# TGA3042.net
KiCad netlist of a schematic drawn in Altium Designer
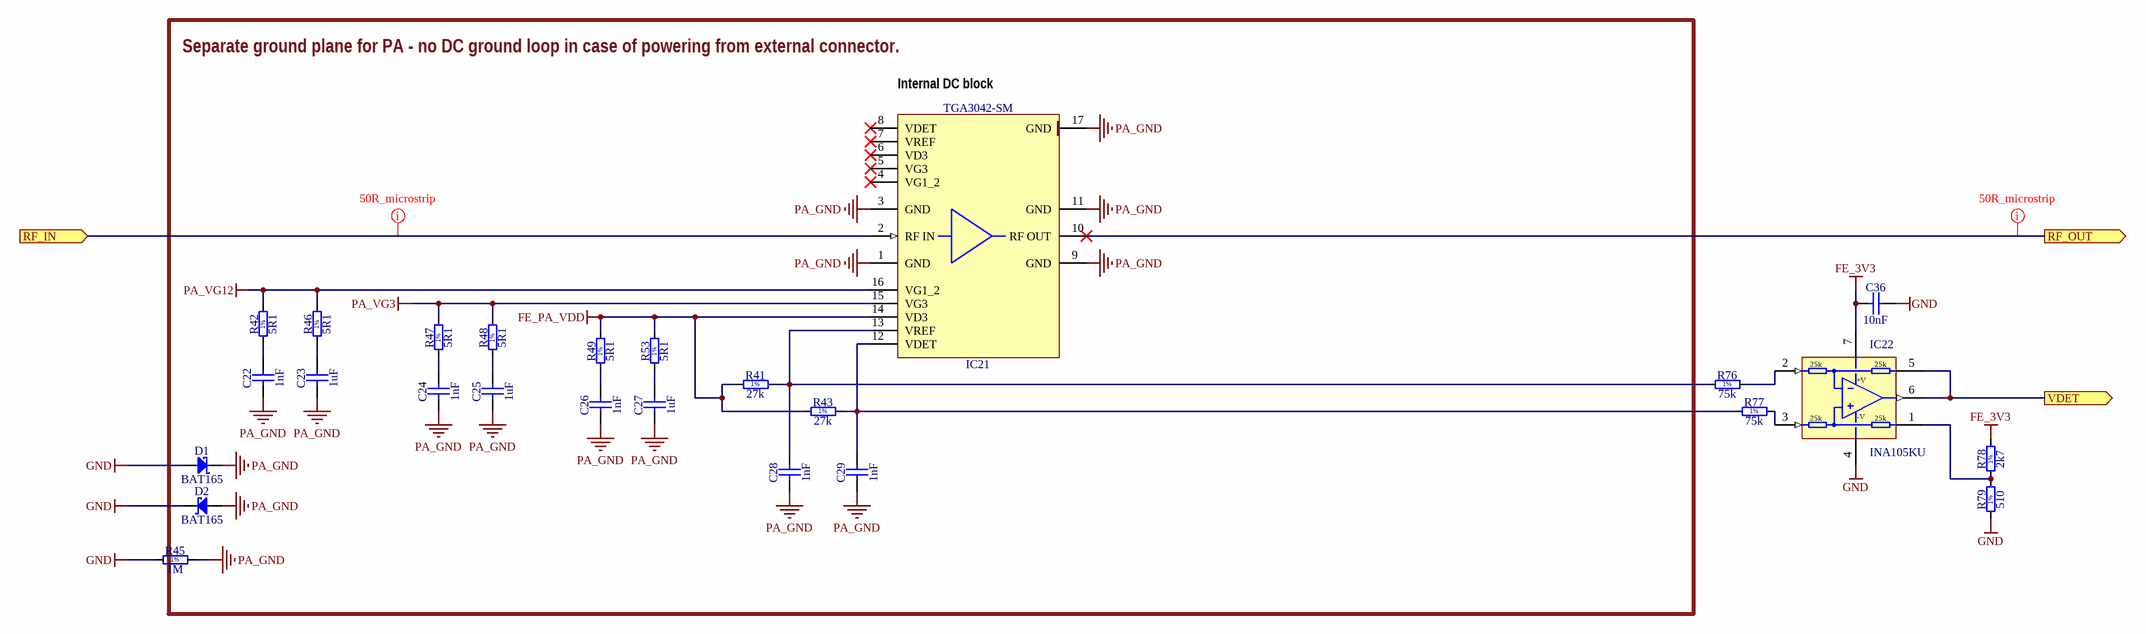
[diagram p0: TGA3042.SchDoc]

(export (version "E")
  (design (tool "Eeschema 10.0.6"))
  (components
    (comp (ref "C22")
      (value "1nF")
      (footprint "CAPC1005X55N")
      (description "Non-polarised capacitor")
      (fields
        (field (name "PART NUMBER") "CC0402_1NF_50V_10%_X7R")
        (field (name "VOLTAGE") "50V")
        (field (name "AUTHOR") "CERN DEM JLC")
      )
      (libsource (lib "Capacitors") (part "Capacitor - non polarized"))
    )
    (comp (ref "C23")
      (value "1uF")
      (footprint "CAPC3216X140N")
      (description "Non-polarised capacitor")
      (fields
        (field (name "PART NUMBER") "CC1206_1UF_50V_10%_X7R")
        (field (name "VOLTAGE") "50V")
        (field (name "AUTHOR") "CERN DEM JLC")
      )
      (libsource (lib "Capacitors") (part "Capacitor - non polarized"))
    )
    (comp (ref "C24")
      (value "1nF")
      (footprint "CAPC1005X55N")
      (description "Non-polarised capacitor")
      (fields
        (field (name "PART NUMBER") "CC0402_1NF_50V_10%_X7R")
        (field (name "VOLTAGE") "50V")
        (field (name "AUTHOR") "CERN DEM JLC")
      )
      (libsource (lib "Capacitors") (part "Capacitor - non polarized"))
    )
    (comp (ref "C25")
      (value "1uF")
      (footprint "CAPC3216X140N")
      (description "Non-polarised capacitor")
      (fields
        (field (name "PART NUMBER") "CC1206_1UF_50V_10%_X7R")
        (field (name "VOLTAGE") "50V")
        (field (name "AUTHOR") "CERN DEM JLC")
      )
      (libsource (lib "Capacitors") (part "Capacitor - non polarized"))
    )
    (comp (ref "C26")
      (value "1nF")
      (footprint "CAPC1005X55N")
      (description "Non-polarised capacitor")
      (fields
        (field (name "PART NUMBER") "CC0402_1NF_50V_10%_X7R")
        (field (name "VOLTAGE") "50V")
        (field (name "AUTHOR") "CERN DEM JLC")
      )
      (libsource (lib "Capacitors") (part "Capacitor - non polarized"))
    )
    (comp (ref "C27")
      (value "1uF")
      (footprint "CAPC3216X140N")
      (description "Non-polarised capacitor")
      (fields
        (field (name "PART NUMBER") "CC1206_1UF_50V_10%_X7R")
        (field (name "VOLTAGE") "50V")
        (field (name "AUTHOR") "CERN DEM JLC")
      )
      (libsource (lib "Capacitors") (part "Capacitor - non polarized"))
    )
    (comp (ref "C28")
      (value "1nF")
      (footprint "CAPC1005X55N")
      (description "Non-polarised capacitor")
      (fields
        (field (name "PART NUMBER") "CC0402_1NF_50V_10%_X7R")
        (field (name "VOLTAGE") "50V")
        (field (name "AUTHOR") "CERN DEM JLC")
      )
      (libsource (lib "Capacitors") (part "Capacitor - non polarized"))
    )
    (comp (ref "C29")
      (value "1nF")
      (footprint "CAPC1005X55N")
      (description "Non-polarised capacitor")
      (fields
        (field (name "PART NUMBER") "CC0402_1NF_50V_10%_X7R")
        (field (name "VOLTAGE") "50V")
        (field (name "AUTHOR") "CERN DEM JLC")
      )
      (libsource (lib "Capacitors") (part "Capacitor - non polarized"))
    )
    (comp (ref "C36")
      (value "10nF")
      (footprint "CAPC1005X55N")
      (description "Non-polarised capacitor")
      (fields
        (field (name "PART NUMBER") "CC0402_10NF_50V_10%_X7R")
        (field (name "VOLTAGE") "50V")
        (field (name "AUTHOR") "CERN DEM MR")
      )
      (libsource (lib "Capacitors") (part "Capacitor - non polarized"))
    )
    (comp (ref "D1")
      (value "BAT165")
      (footprint "SOD2512X110N")
      (description "Schottky Diode")
      (fields
        (field (name "VOLTAGE") "40V")
        (field (name "POWER") "750mA")
        (field (name "AUTHOR") "CERN DEM JLC")
      )
      (libsource (lib "ICs And Semiconductors") (part "Diode Schottky"))
    )
    (comp (ref "D2")
      (value "BAT165")
      (footprint "SOD2512X110N")
      (description "Schottky Diode")
      (fields
        (field (name "VOLTAGE") "40V")
        (field (name "POWER") "750mA")
        (field (name "AUTHOR") "CERN DEM JLC")
      )
      (libsource (lib "ICs And Semiconductors") (part "Diode Schottky"))
    )
    (comp (ref "IC21")
      (value "TGA3042-SM")
      (footprint "QORVO_TGA3042-SM")
      (description "7-10.5GHz 4.5W GaN Power Amplifier")
      (fields (field (name "MANUFACTURER") "QORVO") (field (name "AUTHOR") "CERN DEM JLC"))
      (libsource (lib "FMC_SDR") (part "TGA3042-SM"))
    )
    (comp (ref "IC22")
      (value "INA105KU")
      (footprint "SOIC127P600X175-8N")
      (description "Precision, Unity-Gain Differential Amplifier")
      (fields (field (name "MANUFACTURER") "TEXAS INSTRUMENTS") (field (name "AUTHOR") "CERN DEM JLC"))
      (libsource (lib "ICs And Semiconductors") (part "INA105K"))
    )
    (comp (ref "R41")
      (value "27k")
      (footprint "RESC1005X40N")
      (description "Resistor - 1%")
      (fields
        (field (name "PART NUMBER") "R0402_27K_1%_0.0625W_100PPM")
        (field (name "POWER") "0.0625W")
        (field (name "AUTHOR") "CERN DEM JLC")
      )
      (libsource (lib "Resistors") (part "Resistor - 1%"))
    )
    (comp (ref "R42")
      (value "5R1")
      (footprint "RESC1005X40N")
      (description "Resistor - 1%")
      (fields
        (field (name "PART NUMBER") "R0402_5R1_1%_0.0625W_100PPM")
        (field (name "POWER") "0.0625W")
        (field (name "AUTHOR") "CERN DEM MR")
      )
      (libsource (lib "Resistors") (part "Resistor - 1%"))
    )
    (comp (ref "R43")
      (value "27k")
      (footprint "RESC1005X40N")
      (description "Resistor - 1%")
      (fields
        (field (name "PART NUMBER") "R0402_27K_1%_0.0625W_100PPM")
        (field (name "POWER") "0.0625W")
        (field (name "AUTHOR") "CERN DEM JLC")
      )
      (libsource (lib "Resistors") (part "Resistor - 1%"))
    )
    (comp (ref "R45")
      (value "1M")
      (footprint "RESC1005X40N")
      (description "Resistor - 1%")
      (fields
        (field (name "PART NUMBER") "R0402_1M_1%_0.0625W_100PPM")
        (field (name "POWER") "0.0625W")
        (field (name "AUTHOR") "CERN DEM JLC")
      )
      (libsource (lib "Resistors") (part "Resistor - 1%"))
    )
    (comp (ref "R46")
      (value "5R1")
      (footprint "RESC1005X40N")
      (description "Resistor - 1%")
      (fields
        (field (name "PART NUMBER") "R0402_5R1_1%_0.0625W_100PPM")
        (field (name "POWER") "0.0625W")
        (field (name "AUTHOR") "CERN DEM MR")
      )
      (libsource (lib "Resistors") (part "Resistor - 1%"))
    )
    (comp (ref "R47")
      (value "5R1")
      (footprint "RESC1005X40N")
      (description "Resistor - 1%")
      (fields
        (field (name "PART NUMBER") "R0402_5R1_1%_0.0625W_100PPM")
        (field (name "POWER") "0.0625W")
        (field (name "AUTHOR") "CERN DEM MR")
      )
      (libsource (lib "Resistors") (part "Resistor - 1%"))
    )
    (comp (ref "R48")
      (value "5R1")
      (footprint "RESC1005X40N")
      (description "Resistor - 1%")
      (fields
        (field (name "PART NUMBER") "R0402_5R1_1%_0.0625W_100PPM")
        (field (name "POWER") "0.0625W")
        (field (name "AUTHOR") "CERN DEM MR")
      )
      (libsource (lib "Resistors") (part "Resistor - 1%"))
    )
    (comp (ref "R49")
      (value "5R1")
      (footprint "RESC1005X40N")
      (description "Resistor - 1%")
      (fields
        (field (name "PART NUMBER") "R0402_5R1_1%_0.0625W_100PPM")
        (field (name "POWER") "0.0625W")
        (field (name "AUTHOR") "CERN DEM MR")
      )
      (libsource (lib "Resistors") (part "Resistor - 1%"))
    )
    (comp (ref "R53")
      (value "5R1")
      (footprint "RESC1005X40N")
      (description "Resistor - 1%")
      (fields
        (field (name "PART NUMBER") "R0402_5R1_1%_0.0625W_100PPM")
        (field (name "POWER") "0.0625W")
        (field (name "AUTHOR") "CERN DEM MR")
      )
      (libsource (lib "Resistors") (part "Resistor - 1%"))
    )
    (comp (ref "R76")
      (value "75k")
      (footprint "RESC1608X55N")
      (description "Resistor - 1%")
      (fields
        (field (name "PART NUMBER") "R0603_75K_1%_0.1W_100PPM")
        (field (name "POWER") "0.1W")
        (field (name "AUTHOR") "CERN DEM JLC")
      )
      (libsource (lib "Resistors") (part "Resistor - 1%"))
    )
    (comp (ref "R77")
      (value "75k")
      (footprint "RESC1608X55N")
      (description "Resistor - 1%")
      (fields
        (field (name "PART NUMBER") "R0603_75K_1%_0.1W_100PPM")
        (field (name "POWER") "0.1W")
        (field (name "AUTHOR") "CERN DEM JLC")
      )
      (libsource (lib "Resistors") (part "Resistor - 1%"))
    )
    (comp (ref "R78")
      (value "2k7")
      (footprint "RESC1608X55N")
      (description "Resistor - 1%")
      (fields
        (field (name "PART NUMBER") "R0603_2K7_1%_0.1W_100PPM")
        (field (name "POWER") "0.1W")
        (field (name "AUTHOR") "CERN DEM JLC")
      )
      (libsource (lib "Resistors") (part "Resistor - 1%"))
    )
    (comp (ref "R79")
      (value "510")
      (footprint "RESC1608X55N")
      (description "Resistor - 1%")
      (fields
        (field (name "PART NUMBER") "R0603_510R_1%_0.1W_100PPM")
        (field (name "POWER") "0.1W")
        (field (name "AUTHOR") "CERN DEM JLC")
      )
      (libsource (lib "Resistors") (part "Resistor - 1%"))
    )
  )
  (nets
    (net (code "1") (name "/RF_IN") (class "Default")
      (node (ref "IC21") (pin "2") (pinfunction "RF_IN_2") (pintype "input"))
    )
    (net (code "2") (name "/RF_OUT") (class "Default")
      (node (ref "IC21") (pin "10") (pinfunction "RF_OUT_10") (pintype "power_in+no_connect"))
    )
    (net (code "3") (name "/VDET") (class "Default")
      (node (ref "IC22") (pin "5") (pinfunction "SENS_5") (pintype "passive"))
      (node (ref "IC22") (pin "6") (pinfunction "OUT_6") (pintype "output"))
    )
    (net (code "4") (name "FE_3V3") (class "Default")
      (node (ref "C36") (pin "1") (pinfunction "1_1") (pintype "passive"))
      (node (ref "IC22") (pin "7") (pinfunction "+VCC_7") (pintype "power_in"))
      (node (ref "R78") (pin "2") (pinfunction "2_2") (pintype "passive"))
    )
    (net (code "5") (name "FE_PA_VDD") (class "Default")
      (node (ref "IC21") (pin "14") (pinfunction "VD3_14") (pintype "power_in"))
      (node (ref "R41") (pin "1") (pinfunction "1_1") (pintype "passive"))
      (node (ref "R43") (pin "1") (pinfunction "1_1") (pintype "passive"))
      (node (ref "R49") (pin "2") (pinfunction "2_2") (pintype "passive"))
      (node (ref "R53") (pin "2") (pinfunction "2_2") (pintype "passive"))
    )
    (net (code "6") (name "GND") (class "Default")
      (node (ref "C36") (pin "2") (pinfunction "2_2") (pintype "passive"))
      (node (ref "D1") (pin "2") (pinfunction "A_2") (pintype "passive"))
      (node (ref "D2") (pin "1") (pinfunction "C_1") (pintype "passive"))
      (node (ref "IC22") (pin "4") (pinfunction "-VEE_4") (pintype "power_in"))
      (node (ref "R45") (pin "1") (pinfunction "1_1") (pintype "passive"))
      (node (ref "R79") (pin "1") (pinfunction "1_1") (pintype "passive"))
    )
    (net (code "7") (name "Net-(C22-Pad2)") (class "Default")
      (node (ref "C22") (pin "2") (pinfunction "2_2") (pintype "passive"))
      (node (ref "R42") (pin "1") (pinfunction "1_1") (pintype "passive"))
    )
    (net (code "8") (name "Net-(C23-Pad2)") (class "Default")
      (node (ref "C23") (pin "2") (pinfunction "2_2") (pintype "passive"))
      (node (ref "R46") (pin "1") (pinfunction "1_1") (pintype "passive"))
    )
    (net (code "9") (name "Net-(C24-Pad2)") (class "Default")
      (node (ref "C24") (pin "2") (pinfunction "2_2") (pintype "passive"))
      (node (ref "R47") (pin "1") (pinfunction "1_1") (pintype "passive"))
    )
    (net (code "10") (name "Net-(C25-Pad2)") (class "Default")
      (node (ref "C25") (pin "2") (pinfunction "2_2") (pintype "passive"))
      (node (ref "R48") (pin "1") (pinfunction "1_1") (pintype "passive"))
    )
    (net (code "11") (name "Net-(C26-Pad2)") (class "Default")
      (node (ref "C26") (pin "2") (pinfunction "2_2") (pintype "passive"))
      (node (ref "R49") (pin "1") (pinfunction "1_1") (pintype "passive"))
    )
    (net (code "12") (name "Net-(C27-Pad2)") (class "Default")
      (node (ref "C27") (pin "2") (pinfunction "2_2") (pintype "passive"))
      (node (ref "R53") (pin "1") (pinfunction "1_1") (pintype "passive"))
    )
    (net (code "13") (name "Net-(C28-Pad2)") (class "Default")
      (node (ref "C28") (pin "2") (pinfunction "2_2") (pintype "passive"))
      (node (ref "IC21") (pin "13") (pinfunction "VREF_13") (pintype "power_in"))
      (node (ref "R41") (pin "2") (pinfunction "2_2") (pintype "passive"))
      (node (ref "R76") (pin "1") (pinfunction "1_1") (pintype "passive"))
    )
    (net (code "14") (name "Net-(C29-Pad2)") (class "Default")
      (node (ref "C29") (pin "2") (pinfunction "2_2") (pintype "passive"))
      (node (ref "IC21") (pin "12") (pinfunction "VDET_12") (pintype "power_in"))
      (node (ref "R43") (pin "2") (pinfunction "2_2") (pintype "passive"))
      (node (ref "R77") (pin "1") (pinfunction "1_1") (pintype "passive"))
    )
    (net (code "15") (name "Net-(IC22-IN+)") (class "Default")
      (node (ref "IC22") (pin "3") (pinfunction "IN+_3") (pintype "input"))
      (node (ref "R77") (pin "2") (pinfunction "2_2") (pintype "passive"))
    )
    (net (code "16") (name "Net-(IC22-IN-)") (class "Default")
      (node (ref "IC22") (pin "2") (pinfunction "IN-_2") (pintype "input"))
      (node (ref "R76") (pin "2") (pinfunction "2_2") (pintype "passive"))
    )
    (net (code "17") (name "Net-(IC22-REF)") (class "Default")
      (node (ref "IC22") (pin "1") (pinfunction "REF_1") (pintype "passive"))
      (node (ref "R78") (pin "1") (pinfunction "1_1") (pintype "passive"))
      (node (ref "R79") (pin "2") (pinfunction "2_2") (pintype "passive"))
    )
    (net (code "18") (name "PA_GND") (class "Default")
      (node (ref "C22") (pin "1") (pinfunction "1_1") (pintype "passive"))
      (node (ref "C23") (pin "1") (pinfunction "1_1") (pintype "passive"))
      (node (ref "C24") (pin "1") (pinfunction "1_1") (pintype "passive"))
      (node (ref "C25") (pin "1") (pinfunction "1_1") (pintype "passive"))
      (node (ref "C26") (pin "1") (pinfunction "1_1") (pintype "passive"))
      (node (ref "C27") (pin "1") (pinfunction "1_1") (pintype "passive"))
      (node (ref "C28") (pin "1") (pinfunction "1_1") (pintype "passive"))
      (node (ref "C29") (pin "1") (pinfunction "1_1") (pintype "passive"))
      (node (ref "D1") (pin "1") (pinfunction "C_1") (pintype "passive"))
      (node (ref "D2") (pin "2") (pinfunction "A_2") (pintype "passive"))
      (node (ref "IC21") (pin "1") (pinfunction "GND_1") (pintype "power_in"))
      (node (ref "IC21") (pin "11") (pinfunction "GND_11") (pintype "power_in"))
      (node (ref "IC21") (pin "17") (pinfunction "GND_17") (pintype "power_in"))
      (node (ref "IC21") (pin "3") (pinfunction "GND_3") (pintype "power_in"))
      (node (ref "IC21") (pin "9") (pinfunction "GND_9") (pintype "power_in"))
      (node (ref "R45") (pin "2") (pinfunction "2_2") (pintype "passive"))
    )
    (net (code "19") (name "PA_VG3") (class "Default")
      (node (ref "IC21") (pin "15") (pinfunction "VG3_15") (pintype "power_in"))
      (node (ref "R47") (pin "2") (pinfunction "2_2") (pintype "passive"))
      (node (ref "R48") (pin "2") (pinfunction "2_2") (pintype "passive"))
    )
    (net (code "20") (name "PA_VG12") (class "Default")
      (node (ref "IC21") (pin "16") (pinfunction "VG1_2_16") (pintype "power_in"))
      (node (ref "R42") (pin "2") (pinfunction "2_2") (pintype "passive"))
      (node (ref "R46") (pin "2") (pinfunction "2_2") (pintype "passive"))
    )
    (net (code "21") (name "unconnected-(IC21-VD3-Pad6)") (class "Default")
      (node (ref "IC21") (pin "6") (pinfunction "VD3_6") (pintype "power_in+no_connect"))
    )
    (net (code "22") (name "unconnected-(IC21-VDET-Pad8)") (class "Default")
      (node (ref "IC21") (pin "8") (pinfunction "VDET_8") (pintype "power_in+no_connect"))
    )
    (net (code "23") (name "unconnected-(IC21-VG1_2-Pad4)") (class "Default")
      (node (ref "IC21") (pin "4") (pinfunction "VG1_2_4") (pintype "power_in+no_connect"))
    )
    (net (code "24") (name "unconnected-(IC21-VG3-Pad5)") (class "Default")
      (node (ref "IC21") (pin "5") (pinfunction "VG3_5") (pintype "power_in+no_connect"))
    )
    (net (code "25") (name "unconnected-(IC21-VREF-Pad7)") (class "Default")
      (node (ref "IC21") (pin "7") (pinfunction "VREF_7") (pintype "power_in+no_connect"))
    )
  )
)
